# highpower-new5pad.net
KiCad netlist of a schematic drawn in EAGLE
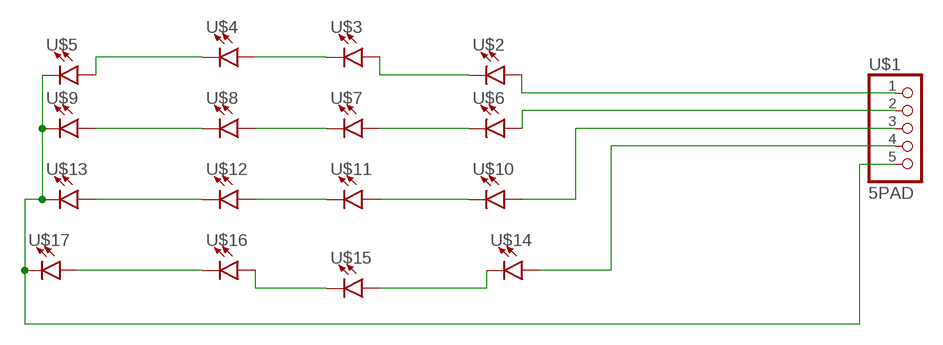
[diagram p0: schematic, sheet 1]

(export (version "E")
  (design (tool "Eeschema 10.0.6"))
  (components
    (comp (ref "U$1")
      (value "5PAD")
      (footprint "eagle-import:1X05SMD_90")
      (libsource (lib "eagle-import") (part "5PAD"))
    )
    (comp (ref "U$2")
      (value "LEDHIGHPOWER")
      (footprint "eagle-import:HIGHPOWERLED")
      (libsource (lib "eagle-import") (part "LEDHIGHPOWER"))
    )
    (comp (ref "U$3")
      (value "LEDHIGHPOWER")
      (footprint "eagle-import:HIGHPOWERLED")
      (libsource (lib "eagle-import") (part "LEDHIGHPOWER"))
    )
    (comp (ref "U$4")
      (value "LEDHIGHPOWER")
      (footprint "eagle-import:HIGHPOWERLED")
      (libsource (lib "eagle-import") (part "LEDHIGHPOWER"))
    )
    (comp (ref "U$5")
      (value "LEDHIGHPOWER")
      (footprint "eagle-import:HIGHPOWERLED")
      (libsource (lib "eagle-import") (part "LEDHIGHPOWER"))
    )
    (comp (ref "U$6")
      (value "LEDHIGHPOWER")
      (footprint "eagle-import:HIGHPOWERLED")
      (libsource (lib "eagle-import") (part "LEDHIGHPOWER"))
    )
    (comp (ref "U$7")
      (value "LEDHIGHPOWER")
      (footprint "eagle-import:HIGHPOWERLED")
      (libsource (lib "eagle-import") (part "LEDHIGHPOWER"))
    )
    (comp (ref "U$8")
      (value "LEDHIGHPOWER")
      (footprint "eagle-import:HIGHPOWERLED")
      (libsource (lib "eagle-import") (part "LEDHIGHPOWER"))
    )
    (comp (ref "U$9")
      (value "LEDHIGHPOWER")
      (footprint "eagle-import:HIGHPOWERLED")
      (libsource (lib "eagle-import") (part "LEDHIGHPOWER"))
    )
    (comp (ref "U$10")
      (value "LEDHIGHPOWER")
      (footprint "eagle-import:HIGHPOWERLED")
      (libsource (lib "eagle-import") (part "LEDHIGHPOWER"))
    )
    (comp (ref "U$11")
      (value "LEDHIGHPOWER")
      (footprint "eagle-import:HIGHPOWERLED")
      (libsource (lib "eagle-import") (part "LEDHIGHPOWER"))
    )
    (comp (ref "U$12")
      (value "LEDHIGHPOWER")
      (footprint "eagle-import:HIGHPOWERLED")
      (libsource (lib "eagle-import") (part "LEDHIGHPOWER"))
    )
    (comp (ref "U$13")
      (value "LEDHIGHPOWER")
      (footprint "eagle-import:HIGHPOWERLED")
      (libsource (lib "eagle-import") (part "LEDHIGHPOWER"))
    )
    (comp (ref "U$14")
      (value "LEDHIGHPOWER")
      (footprint "eagle-import:HIGHPOWERLED")
      (libsource (lib "eagle-import") (part "LEDHIGHPOWER"))
    )
    (comp (ref "U$15")
      (value "LEDHIGHPOWER")
      (footprint "eagle-import:HIGHPOWERLED")
      (libsource (lib "eagle-import") (part "LEDHIGHPOWER"))
    )
    (comp (ref "U$16")
      (value "LEDHIGHPOWER")
      (footprint "eagle-import:HIGHPOWERLED")
      (libsource (lib "eagle-import") (part "LEDHIGHPOWER"))
    )
    (comp (ref "U$17")
      (value "LEDHIGHPOWER")
      (footprint "eagle-import:HIGHPOWERLED")
      (libsource (lib "eagle-import") (part "LEDHIGHPOWER"))
    )
  )
  (nets
    (net (code "1") (name "Net-(U$2-A)") (class "Default")
      (node (ref "U$1") (pin "1") (pinfunction "1_1") (pintype "passive"))
      (node (ref "U$2") (pin "PO") (pinfunction "A_PO") (pintype "passive"))
    )
    (net (code "2") (name "Net-(U$2-C)") (class "Default")
      (node (ref "U$2") (pin "PI") (pinfunction "C_PI") (pintype "passive"))
      (node (ref "U$3") (pin "PO") (pinfunction "A_PO") (pintype "passive"))
    )
    (net (code "3") (name "Net-(U$3-C)") (class "Default")
      (node (ref "U$3") (pin "PI") (pinfunction "C_PI") (pintype "passive"))
      (node (ref "U$4") (pin "PO") (pinfunction "A_PO") (pintype "passive"))
    )
    (net (code "4") (name "Net-(U$4-C)") (class "Default")
      (node (ref "U$4") (pin "PI") (pinfunction "C_PI") (pintype "passive"))
      (node (ref "U$5") (pin "PO") (pinfunction "A_PO") (pintype "passive"))
    )
    (net (code "5") (name "Net-(U$6-A)") (class "Default")
      (node (ref "U$1") (pin "2") (pinfunction "2_2") (pintype "passive"))
      (node (ref "U$6") (pin "PO") (pinfunction "A_PO") (pintype "passive"))
    )
    (net (code "6") (name "Net-(U$6-C)") (class "Default")
      (node (ref "U$6") (pin "PI") (pinfunction "C_PI") (pintype "passive"))
      (node (ref "U$7") (pin "PO") (pinfunction "A_PO") (pintype "passive"))
    )
    (net (code "7") (name "Net-(U$7-C)") (class "Default")
      (node (ref "U$7") (pin "PI") (pinfunction "C_PI") (pintype "passive"))
      (node (ref "U$8") (pin "PO") (pinfunction "A_PO") (pintype "passive"))
    )
    (net (code "8") (name "Net-(U$8-C)") (class "Default")
      (node (ref "U$8") (pin "PI") (pinfunction "C_PI") (pintype "passive"))
      (node (ref "U$9") (pin "PO") (pinfunction "A_PO") (pintype "passive"))
    )
    (net (code "9") (name "Net-(U$10-A)") (class "Default")
      (node (ref "U$1") (pin "3") (pinfunction "3_3") (pintype "passive"))
      (node (ref "U$10") (pin "PO") (pinfunction "A_PO") (pintype "passive"))
    )
    (net (code "10") (name "Net-(U$10-C)") (class "Default")
      (node (ref "U$10") (pin "PI") (pinfunction "C_PI") (pintype "passive"))
      (node (ref "U$11") (pin "PO") (pinfunction "A_PO") (pintype "passive"))
    )
    (net (code "11") (name "Net-(U$11-C)") (class "Default")
      (node (ref "U$11") (pin "PI") (pinfunction "C_PI") (pintype "passive"))
      (node (ref "U$12") (pin "PO") (pinfunction "A_PO") (pintype "passive"))
    )
    (net (code "12") (name "Net-(U$12-C)") (class "Default")
      (node (ref "U$12") (pin "PI") (pinfunction "C_PI") (pintype "passive"))
      (node (ref "U$13") (pin "PO") (pinfunction "A_PO") (pintype "passive"))
    )
    (net (code "13") (name "Net-(U$13-C)") (class "Default")
      (node (ref "U$1") (pin "5") (pinfunction "5_5") (pintype "passive"))
      (node (ref "U$13") (pin "PI") (pinfunction "C_PI") (pintype "passive"))
      (node (ref "U$17") (pin "PI") (pinfunction "C_PI") (pintype "passive"))
      (node (ref "U$5") (pin "PI") (pinfunction "C_PI") (pintype "passive"))
      (node (ref "U$9") (pin "PI") (pinfunction "C_PI") (pintype "passive"))
    )
    (net (code "14") (name "Net-(U$14-A)") (class "Default")
      (node (ref "U$1") (pin "4") (pinfunction "4_4") (pintype "passive"))
      (node (ref "U$14") (pin "PO") (pinfunction "A_PO") (pintype "passive"))
    )
    (net (code "15") (name "Net-(U$14-C)") (class "Default")
      (node (ref "U$14") (pin "PI") (pinfunction "C_PI") (pintype "passive"))
      (node (ref "U$15") (pin "PO") (pinfunction "A_PO") (pintype "passive"))
    )
    (net (code "16") (name "Net-(U$15-C)") (class "Default")
      (node (ref "U$15") (pin "PI") (pinfunction "C_PI") (pintype "passive"))
      (node (ref "U$16") (pin "PO") (pinfunction "A_PO") (pintype "passive"))
    )
    (net (code "17") (name "Net-(U$16-C)") (class "Default")
      (node (ref "U$16") (pin "PI") (pinfunction "C_PI") (pintype "passive"))
      (node (ref "U$17") (pin "PO") (pinfunction "A_PO") (pintype "passive"))
    )
  )
)
